# 74HC595.net
KiCad netlist of a schematic drawn in Altium Designer
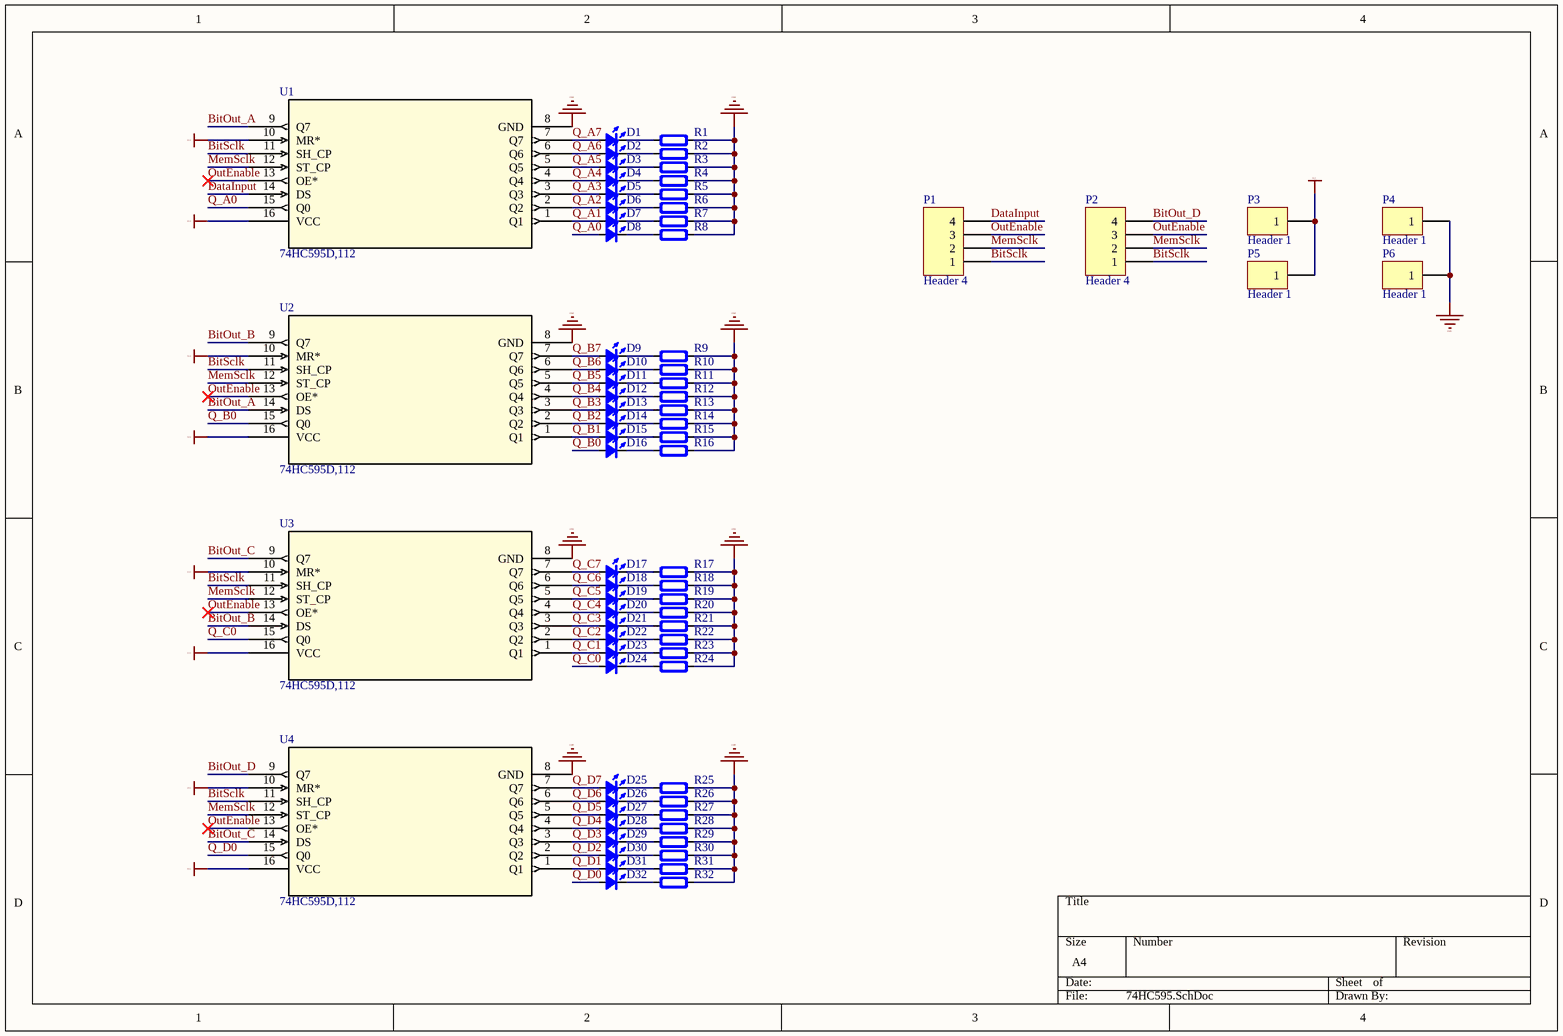
[diagram p0: 74HC595.SchDoc]

(export (version "E")
  (design (tool "Eeschema 10.0.6"))
  (components
    (comp (ref "D1")
      (value "color?")
      (footprint "PCB_ActiveLED:LED_0805_RED")
      (description "LED")
      (libsource (lib "EspPov") (part "LED_0805"))
    )
    (comp (ref "D2")
      (value "color?")
      (footprint "PCB_ActiveLED:LED_0805_RED")
      (description "LED")
      (libsource (lib "EspPov") (part "LED_0805"))
    )
    (comp (ref "D3")
      (value "color?")
      (footprint "PCB_ActiveLED:LED_0805_RED")
      (description "LED")
      (libsource (lib "EspPov") (part "LED_0805"))
    )
    (comp (ref "D4")
      (value "color?")
      (footprint "PCB_ActiveLED:LED_0805_RED")
      (description "LED")
      (libsource (lib "EspPov") (part "LED_0805"))
    )
    (comp (ref "D5")
      (value "color?")
      (footprint "PCB_ActiveLED:LED_0805_RED")
      (description "LED")
      (libsource (lib "EspPov") (part "LED_0805"))
    )
    (comp (ref "D6")
      (value "color?")
      (footprint "PCB_ActiveLED:LED_0805_RED")
      (description "LED")
      (libsource (lib "EspPov") (part "LED_0805"))
    )
    (comp (ref "D7")
      (value "color?")
      (footprint "PCB_ActiveLED:LED_0805_RED")
      (description "LED")
      (libsource (lib "EspPov") (part "LED_0805"))
    )
    (comp (ref "D8")
      (value "color?")
      (footprint "PCB_ActiveLED:LED_0805_RED")
      (description "LED")
      (libsource (lib "EspPov") (part "LED_0805"))
    )
    (comp (ref "D9")
      (value "color?")
      (footprint "PCB_ActiveLED:LED_0805_RED")
      (description "LED")
      (libsource (lib "EspPov") (part "LED_0805"))
    )
    (comp (ref "D10")
      (value "color?")
      (footprint "PCB_ActiveLED:LED_0805_RED")
      (description "LED")
      (libsource (lib "EspPov") (part "LED_0805"))
    )
    (comp (ref "D11")
      (value "color?")
      (footprint "PCB_ActiveLED:LED_0805_RED")
      (description "LED")
      (libsource (lib "EspPov") (part "LED_0805"))
    )
    (comp (ref "D12")
      (value "color?")
      (footprint "PCB_ActiveLED:LED_0805_RED")
      (description "LED")
      (libsource (lib "EspPov") (part "LED_0805"))
    )
    (comp (ref "D13")
      (value "color?")
      (footprint "PCB_ActiveLED:LED_0805_RED")
      (description "LED")
      (libsource (lib "EspPov") (part "LED_0805"))
    )
    (comp (ref "D14")
      (value "color?")
      (footprint "PCB_ActiveLED:LED_0805_RED")
      (description "LED")
      (libsource (lib "EspPov") (part "LED_0805"))
    )
    (comp (ref "D15")
      (value "color?")
      (footprint "PCB_ActiveLED:LED_0805_RED")
      (description "LED")
      (libsource (lib "EspPov") (part "LED_0805"))
    )
    (comp (ref "D16")
      (value "color?")
      (footprint "PCB_ActiveLED:LED_0805_RED")
      (description "LED")
      (libsource (lib "EspPov") (part "LED_0805"))
    )
    (comp (ref "D17")
      (value "color?")
      (footprint "PCB_ActiveLED:LED_0805_RED")
      (description "LED")
      (libsource (lib "EspPov") (part "LED_0805"))
    )
    (comp (ref "D18")
      (value "color?")
      (footprint "PCB_ActiveLED:LED_0805_RED")
      (description "LED")
      (libsource (lib "EspPov") (part "LED_0805"))
    )
    (comp (ref "D19")
      (value "color?")
      (footprint "PCB_ActiveLED:LED_0805_RED")
      (description "LED")
      (libsource (lib "EspPov") (part "LED_0805"))
    )
    (comp (ref "D20")
      (value "color?")
      (footprint "PCB_ActiveLED:LED_0805_RED")
      (description "LED")
      (libsource (lib "EspPov") (part "LED_0805"))
    )
    (comp (ref "D21")
      (value "color?")
      (footprint "PCB_ActiveLED:LED_0805_RED")
      (description "LED")
      (libsource (lib "EspPov") (part "LED_0805"))
    )
    (comp (ref "D22")
      (value "color?")
      (footprint "PCB_ActiveLED:LED_0805_RED")
      (description "LED")
      (libsource (lib "EspPov") (part "LED_0805"))
    )
    (comp (ref "D23")
      (value "color?")
      (footprint "PCB_ActiveLED:LED_0805_RED")
      (description "LED")
      (libsource (lib "EspPov") (part "LED_0805"))
    )
    (comp (ref "D24")
      (value "color?")
      (footprint "PCB_ActiveLED:LED_0805_RED")
      (description "LED")
      (libsource (lib "EspPov") (part "LED_0805"))
    )
    (comp (ref "D25")
      (value "color?")
      (footprint "PCB_ActiveLED:LED_0805_RED")
      (description "LED")
      (libsource (lib "EspPov") (part "LED_0805"))
    )
    (comp (ref "D26")
      (value "color?")
      (footprint "PCB_ActiveLED:LED_0805_RED")
      (description "LED")
      (libsource (lib "EspPov") (part "LED_0805"))
    )
    (comp (ref "D27")
      (value "color?")
      (footprint "PCB_ActiveLED:LED_0805_RED")
      (description "LED")
      (libsource (lib "EspPov") (part "LED_0805"))
    )
    (comp (ref "D28")
      (value "color?")
      (footprint "PCB_ActiveLED:LED_0805_RED")
      (description "LED")
      (libsource (lib "EspPov") (part "LED_0805"))
    )
    (comp (ref "D29")
      (value "color?")
      (footprint "PCB_ActiveLED:LED_0805_RED")
      (description "LED")
      (libsource (lib "EspPov") (part "LED_0805"))
    )
    (comp (ref "D30")
      (value "color?")
      (footprint "PCB_ActiveLED:LED_0805_RED")
      (description "LED")
      (libsource (lib "EspPov") (part "LED_0805"))
    )
    (comp (ref "D31")
      (value "color?")
      (footprint "PCB_ActiveLED:LED_0805_RED")
      (description "LED")
      (libsource (lib "EspPov") (part "LED_0805"))
    )
    (comp (ref "D32")
      (value "color?")
      (footprint "PCB_ActiveLED:LED_0805_RED")
      (description "LED")
      (libsource (lib "EspPov") (part "LED_0805"))
    )
    (comp (ref "P1")
      (value "Header 4")
      (footprint "HDR1X4_SOP")
      (description "Header, 4-Pin")
      (fields (field (name "PUBLISHER") "Altium Limited"))
      (libsource (lib "EspPov") (part "Header 4"))
    )
    (comp (ref "P2")
      (value "Header 4")
      (footprint "HDR1X4_SOP")
      (description "Header, 4-Pin")
      (fields (field (name "PUBLISHER") "Altium Limited"))
      (libsource (lib "EspPov") (part "Header 4"))
    )
    (comp (ref "P3")
      (value "Header 1")
      (footprint "HDR1X1_SOP")
      (description "Header, 1-Pin")
      (fields (field (name "PUBLISHER") "Altium Limited"))
      (libsource (lib "EspPov") (part "Header 1"))
    )
    (comp (ref "P4")
      (value "Header 1")
      (footprint "HDR1X1_SOP")
      (description "Header, 1-Pin")
      (fields (field (name "PUBLISHER") "Altium Limited"))
      (libsource (lib "EspPov") (part "Header 1"))
    )
    (comp (ref "P5")
      (value "Header 1")
      (footprint "HDR1X1_SOP")
      (description "Header, 1-Pin")
      (fields (field (name "PUBLISHER") "Altium Limited"))
      (libsource (lib "EspPov") (part "Header 1"))
    )
    (comp (ref "P6")
      (value "Header 1")
      (footprint "HDR1X1_SOP")
      (description "Header, 1-Pin")
      (fields (field (name "PUBLISHER") "Altium Limited"))
      (libsource (lib "EspPov") (part "Header 1"))
    )
    (comp (ref "R1")
      (value "R0805")
      (footprint "RES_0805")
      (description "Resistor")
      (libsource (lib "EspPov") (part "Res_0805"))
    )
    (comp (ref "R2")
      (value "R0805")
      (footprint "RES_0805")
      (description "Resistor")
      (libsource (lib "EspPov") (part "Res_0805"))
    )
    (comp (ref "R3")
      (value "R0805")
      (footprint "RES_0805")
      (description "Resistor")
      (libsource (lib "EspPov") (part "Res_0805"))
    )
    (comp (ref "R4")
      (value "R0805")
      (footprint "RES_0805")
      (description "Resistor")
      (libsource (lib "EspPov") (part "Res_0805"))
    )
    (comp (ref "R5")
      (value "R0805")
      (footprint "RES_0805")
      (description "Resistor")
      (libsource (lib "EspPov") (part "Res_0805"))
    )
    (comp (ref "R6")
      (value "R0805")
      (footprint "RES_0805")
      (description "Resistor")
      (libsource (lib "EspPov") (part "Res_0805"))
    )
    (comp (ref "R7")
      (value "R0805")
      (footprint "RES_0805")
      (description "Resistor")
      (libsource (lib "EspPov") (part "Res_0805"))
    )
    (comp (ref "R8")
      (value "R0805")
      (footprint "RES_0805")
      (description "Resistor")
      (libsource (lib "EspPov") (part "Res_0805"))
    )
    (comp (ref "R9")
      (value "R0805")
      (footprint "RES_0805")
      (description "Resistor")
      (libsource (lib "EspPov") (part "Res_0805"))
    )
    (comp (ref "R10")
      (value "R0805")
      (footprint "RES_0805")
      (description "Resistor")
      (libsource (lib "EspPov") (part "Res_0805"))
    )
    (comp (ref "R11")
      (value "R0805")
      (footprint "RES_0805")
      (description "Resistor")
      (libsource (lib "EspPov") (part "Res_0805"))
    )
    (comp (ref "R12")
      (value "R0805")
      (footprint "RES_0805")
      (description "Resistor")
      (libsource (lib "EspPov") (part "Res_0805"))
    )
    (comp (ref "R13")
      (value "R0805")
      (footprint "RES_0805")
      (description "Resistor")
      (libsource (lib "EspPov") (part "Res_0805"))
    )
    (comp (ref "R14")
      (value "R0805")
      (footprint "RES_0805")
      (description "Resistor")
      (libsource (lib "EspPov") (part "Res_0805"))
    )
    (comp (ref "R15")
      (value "R0805")
      (footprint "RES_0805")
      (description "Resistor")
      (libsource (lib "EspPov") (part "Res_0805"))
    )
    (comp (ref "R16")
      (value "R0805")
      (footprint "RES_0805")
      (description "Resistor")
      (libsource (lib "EspPov") (part "Res_0805"))
    )
    (comp (ref "R17")
      (value "R0805")
      (footprint "RES_0805")
      (description "Resistor")
      (libsource (lib "EspPov") (part "Res_0805"))
    )
    (comp (ref "R18")
      (value "R0805")
      (footprint "RES_0805")
      (description "Resistor")
      (libsource (lib "EspPov") (part "Res_0805"))
    )
    (comp (ref "R19")
      (value "R0805")
      (footprint "RES_0805")
      (description "Resistor")
      (libsource (lib "EspPov") (part "Res_0805"))
    )
    (comp (ref "R20")
      (value "R0805")
      (footprint "RES_0805")
      (description "Resistor")
      (libsource (lib "EspPov") (part "Res_0805"))
    )
    (comp (ref "R21")
      (value "R0805")
      (footprint "RES_0805")
      (description "Resistor")
      (libsource (lib "EspPov") (part "Res_0805"))
    )
    (comp (ref "R22")
      (value "R0805")
      (footprint "RES_0805")
      (description "Resistor")
      (libsource (lib "EspPov") (part "Res_0805"))
    )
    (comp (ref "R23")
      (value "R0805")
      (footprint "RES_0805")
      (description "Resistor")
      (libsource (lib "EspPov") (part "Res_0805"))
    )
    (comp (ref "R24")
      (value "R0805")
      (footprint "RES_0805")
      (description "Resistor")
      (libsource (lib "EspPov") (part "Res_0805"))
    )
    (comp (ref "R25")
      (value "R0805")
      (footprint "RES_0805")
      (description "Resistor")
      (libsource (lib "EspPov") (part "Res_0805"))
    )
    (comp (ref "R26")
      (value "R0805")
      (footprint "RES_0805")
      (description "Resistor")
      (libsource (lib "EspPov") (part "Res_0805"))
    )
    (comp (ref "R27")
      (value "R0805")
      (footprint "RES_0805")
      (description "Resistor")
      (libsource (lib "EspPov") (part "Res_0805"))
    )
    (comp (ref "R28")
      (value "R0805")
      (footprint "RES_0805")
      (description "Resistor")
      (libsource (lib "EspPov") (part "Res_0805"))
    )
    (comp (ref "R29")
      (value "R0805")
      (footprint "RES_0805")
      (description "Resistor")
      (libsource (lib "EspPov") (part "Res_0805"))
    )
    (comp (ref "R30")
      (value "R0805")
      (footprint "RES_0805")
      (description "Resistor")
      (libsource (lib "EspPov") (part "Res_0805"))
    )
    (comp (ref "R31")
      (value "R0805")
      (footprint "RES_0805")
      (description "Resistor")
      (libsource (lib "EspPov") (part "Res_0805"))
    )
    (comp (ref "R32")
      (value "R0805")
      (footprint "RES_0805")
      (description "Resistor")
      (libsource (lib "EspPov") (part "Res_0805"))
    )
    (comp (ref "U1")
      (value "74HC595D,112")
      (footprint "SOT109-1_NEX")
      (description "No Description Available")
      (fields (field (name "COPYRIGHT") "Copyright (C) 2016 Accelerated Designs. All rights reserved"))
      (libsource (lib "EspPov") (part "74HC595D,112"))
    )
    (comp (ref "U2")
      (value "74HC595D,112")
      (footprint "SOT109-1_NEX")
      (description "No Description Available")
      (fields (field (name "COPYRIGHT") "Copyright (C) 2016 Accelerated Designs. All rights reserved"))
      (libsource (lib "EspPov") (part "74HC595D,112"))
    )
    (comp (ref "U3")
      (value "74HC595D,112")
      (footprint "SOT109-1_NEX")
      (description "No Description Available")
      (fields (field (name "COPYRIGHT") "Copyright (C) 2016 Accelerated Designs. All rights reserved"))
      (libsource (lib "EspPov") (part "74HC595D,112"))
    )
    (comp (ref "U4")
      (value "74HC595D,112")
      (footprint "SOT109-1_NEX")
      (description "No Description Available")
      (fields (field (name "COPYRIGHT") "Copyright (C) 2016 Accelerated Designs. All rights reserved"))
      (libsource (lib "EspPov") (part "74HC595D,112"))
    )
  )
  (nets
    (net (code "1") (name "/BitOut_A") (class "Default")
      (node (ref "U1") (pin "9") (pinfunction "Q7_9") (pintype "output"))
      (node (ref "U2") (pin "14") (pinfunction "DS_14") (pintype "input"))
    )
    (net (code "2") (name "/BitOut_B") (class "Default")
      (node (ref "U2") (pin "9") (pinfunction "Q7_9") (pintype "output"))
      (node (ref "U3") (pin "14") (pinfunction "DS_14") (pintype "input"))
    )
    (net (code "3") (name "/BitOut_C") (class "Default")
      (node (ref "U3") (pin "9") (pinfunction "Q7_9") (pintype "output"))
      (node (ref "U4") (pin "14") (pinfunction "DS_14") (pintype "input"))
    )
    (net (code "4") (name "/BitOut_D") (class "Default")
      (node (ref "P2") (pin "4") (pinfunction "4_4") (pintype "passive"))
      (node (ref "U4") (pin "9") (pinfunction "Q7_9") (pintype "output"))
    )
    (net (code "5") (name "/BitSclk") (class "Default")
      (node (ref "P1") (pin "1") (pinfunction "1_1") (pintype "passive"))
      (node (ref "P2") (pin "1") (pinfunction "1_1") (pintype "passive"))
      (node (ref "U1") (pin "11") (pinfunction "SH_CP_11") (pintype "input"))
      (node (ref "U2") (pin "11") (pinfunction "SH_CP_11") (pintype "input"))
      (node (ref "U3") (pin "11") (pinfunction "SH_CP_11") (pintype "input"))
      (node (ref "U4") (pin "11") (pinfunction "SH_CP_11") (pintype "input"))
    )
    (net (code "6") (name "/DataInput") (class "Default")
      (node (ref "P1") (pin "4") (pinfunction "4_4") (pintype "passive"))
      (node (ref "U1") (pin "14") (pinfunction "DS_14") (pintype "input"))
    )
    (net (code "7") (name "/MemSclk") (class "Default")
      (node (ref "P1") (pin "2") (pinfunction "2_2") (pintype "passive"))
      (node (ref "P2") (pin "2") (pinfunction "2_2") (pintype "passive"))
      (node (ref "U1") (pin "12") (pinfunction "ST_CP_12") (pintype "input"))
      (node (ref "U2") (pin "12") (pinfunction "ST_CP_12") (pintype "input"))
      (node (ref "U3") (pin "12") (pinfunction "ST_CP_12") (pintype "input"))
      (node (ref "U4") (pin "12") (pinfunction "ST_CP_12") (pintype "input"))
    )
    (net (code "8") (name "/OutEnable") (class "Default")
      (node (ref "P1") (pin "3") (pinfunction "3_3") (pintype "passive"))
      (node (ref "P2") (pin "3") (pinfunction "3_3") (pintype "passive"))
      (node (ref "U1") (pin "13") (pinfunction "OE*_13") (pintype "output"))
      (node (ref "U2") (pin "13") (pinfunction "OE*_13") (pintype "output"))
      (node (ref "U3") (pin "13") (pinfunction "OE*_13") (pintype "output"))
      (node (ref "U4") (pin "13") (pinfunction "OE*_13") (pintype "output"))
    )
    (net (code "9") (name "/Q_A0") (class "Default")
      (node (ref "D8") (pin "2") (pinfunction "A_2") (pintype "passive"))
      (node (ref "U1") (pin "15") (pinfunction "Q0_15") (pintype "output"))
    )
    (net (code "10") (name "/Q_A1") (class "Default")
      (node (ref "D7") (pin "2") (pinfunction "A_2") (pintype "passive"))
      (node (ref "U1") (pin "1") (pinfunction "Q1_1") (pintype "output"))
    )
    (net (code "11") (name "/Q_A2") (class "Default")
      (node (ref "D6") (pin "2") (pinfunction "A_2") (pintype "passive"))
      (node (ref "U1") (pin "2") (pinfunction "Q2_2") (pintype "output"))
    )
    (net (code "12") (name "/Q_A3") (class "Default")
      (node (ref "D5") (pin "2") (pinfunction "A_2") (pintype "passive"))
      (node (ref "U1") (pin "3") (pinfunction "Q3_3") (pintype "output"))
    )
    (net (code "13") (name "/Q_A4") (class "Default")
      (node (ref "D4") (pin "2") (pinfunction "A_2") (pintype "passive"))
      (node (ref "U1") (pin "4") (pinfunction "Q4_4") (pintype "output"))
    )
    (net (code "14") (name "/Q_A5") (class "Default")
      (node (ref "D3") (pin "2") (pinfunction "A_2") (pintype "passive"))
      (node (ref "U1") (pin "5") (pinfunction "Q5_5") (pintype "output"))
    )
    (net (code "15") (name "/Q_A6") (class "Default")
      (node (ref "D2") (pin "2") (pinfunction "A_2") (pintype "passive"))
      (node (ref "U1") (pin "6") (pinfunction "Q6_6") (pintype "output"))
    )
    (net (code "16") (name "/Q_A7") (class "Default")
      (node (ref "D1") (pin "2") (pinfunction "A_2") (pintype "passive"))
      (node (ref "U1") (pin "7") (pinfunction "Q7_7") (pintype "output"))
    )
    (net (code "17") (name "/Q_B0") (class "Default")
      (node (ref "D16") (pin "2") (pinfunction "A_2") (pintype "passive"))
      (node (ref "U2") (pin "15") (pinfunction "Q0_15") (pintype "output"))
    )
    (net (code "18") (name "/Q_B1") (class "Default")
      (node (ref "D15") (pin "2") (pinfunction "A_2") (pintype "passive"))
      (node (ref "U2") (pin "1") (pinfunction "Q1_1") (pintype "output"))
    )
    (net (code "19") (name "/Q_B2") (class "Default")
      (node (ref "D14") (pin "2") (pinfunction "A_2") (pintype "passive"))
      (node (ref "U2") (pin "2") (pinfunction "Q2_2") (pintype "output"))
    )
    (net (code "20") (name "/Q_B3") (class "Default")
      (node (ref "D13") (pin "2") (pinfunction "A_2") (pintype "passive"))
      (node (ref "U2") (pin "3") (pinfunction "Q3_3") (pintype "output"))
    )
    (net (code "21") (name "/Q_B4") (class "Default")
      (node (ref "D12") (pin "2") (pinfunction "A_2") (pintype "passive"))
      (node (ref "U2") (pin "4") (pinfunction "Q4_4") (pintype "output"))
    )
    (net (code "22") (name "/Q_B5") (class "Default")
      (node (ref "D11") (pin "2") (pinfunction "A_2") (pintype "passive"))
      (node (ref "U2") (pin "5") (pinfunction "Q5_5") (pintype "output"))
    )
    (net (code "23") (name "/Q_B6") (class "Default")
      (node (ref "D10") (pin "2") (pinfunction "A_2") (pintype "passive"))
      (node (ref "U2") (pin "6") (pinfunction "Q6_6") (pintype "output"))
    )
    (net (code "24") (name "/Q_B7") (class "Default")
      (node (ref "D9") (pin "2") (pinfunction "A_2") (pintype "passive"))
      (node (ref "U2") (pin "7") (pinfunction "Q7_7") (pintype "output"))
    )
    (net (code "25") (name "/Q_C0") (class "Default")
      (node (ref "D24") (pin "2") (pinfunction "A_2") (pintype "passive"))
      (node (ref "U3") (pin "15") (pinfunction "Q0_15") (pintype "output"))
    )
    (net (code "26") (name "/Q_C1") (class "Default")
      (node (ref "D23") (pin "2") (pinfunction "A_2") (pintype "passive"))
      (node (ref "U3") (pin "1") (pinfunction "Q1_1") (pintype "output"))
    )
    (net (code "27") (name "/Q_C2") (class "Default")
      (node (ref "D22") (pin "2") (pinfunction "A_2") (pintype "passive"))
      (node (ref "U3") (pin "2") (pinfunction "Q2_2") (pintype "output"))
    )
    (net (code "28") (name "/Q_C3") (class "Default")
      (node (ref "D21") (pin "2") (pinfunction "A_2") (pintype "passive"))
      (node (ref "U3") (pin "3") (pinfunction "Q3_3") (pintype "output"))
    )
    (net (code "29") (name "/Q_C4") (class "Default")
      (node (ref "D20") (pin "2") (pinfunction "A_2") (pintype "passive"))
      (node (ref "U3") (pin "4") (pinfunction "Q4_4") (pintype "output"))
    )
    (net (code "30") (name "/Q_C5") (class "Default")
      (node (ref "D19") (pin "2") (pinfunction "A_2") (pintype "passive"))
      (node (ref "U3") (pin "5") (pinfunction "Q5_5") (pintype "output"))
    )
    (net (code "31") (name "/Q_C6") (class "Default")
      (node (ref "D18") (pin "2") (pinfunction "A_2") (pintype "passive"))
      (node (ref "U3") (pin "6") (pinfunction "Q6_6") (pintype "output"))
    )
    (net (code "32") (name "/Q_C7") (class "Default")
      (node (ref "D17") (pin "2") (pinfunction "A_2") (pintype "passive"))
      (node (ref "U3") (pin "7") (pinfunction "Q7_7") (pintype "output"))
    )
    (net (code "33") (name "/Q_D0") (class "Default")
      (node (ref "D32") (pin "2") (pinfunction "A_2") (pintype "passive"))
      (node (ref "U4") (pin "15") (pinfunction "Q0_15") (pintype "output"))
    )
    (net (code "34") (name "/Q_D1") (class "Default")
      (node (ref "D31") (pin "2") (pinfunction "A_2") (pintype "passive"))
      (node (ref "U4") (pin "1") (pinfunction "Q1_1") (pintype "output"))
    )
    (net (code "35") (name "/Q_D2") (class "Default")
      (node (ref "D30") (pin "2") (pinfunction "A_2") (pintype "passive"))
      (node (ref "U4") (pin "2") (pinfunction "Q2_2") (pintype "output"))
    )
    (net (code "36") (name "/Q_D3") (class "Default")
      (node (ref "D29") (pin "2") (pinfunction "A_2") (pintype "passive"))
      (node (ref "U4") (pin "3") (pinfunction "Q3_3") (pintype "output"))
    )
    (net (code "37") (name "/Q_D4") (class "Default")
      (node (ref "D28") (pin "2") (pinfunction "A_2") (pintype "passive"))
      (node (ref "U4") (pin "4") (pinfunction "Q4_4") (pintype "output"))
    )
    (net (code "38") (name "/Q_D5") (class "Default")
      (node (ref "D27") (pin "2") (pinfunction "A_2") (pintype "passive"))
      (node (ref "U4") (pin "5") (pinfunction "Q5_5") (pintype "output"))
    )
    (net (code "39") (name "/Q_D6") (class "Default")
      (node (ref "D26") (pin "2") (pinfunction "A_2") (pintype "passive"))
      (node (ref "U4") (pin "6") (pinfunction "Q6_6") (pintype "output"))
    )
    (net (code "40") (name "/Q_D7") (class "Default")
      (node (ref "D25") (pin "2") (pinfunction "A_2") (pintype "passive"))
      (node (ref "U4") (pin "7") (pinfunction "Q7_7") (pintype "output"))
    )
    (net (code "41") (name "GND") (class "Default")
      (node (ref "P4") (pin "1") (pinfunction "1_1") (pintype "passive"))
      (node (ref "P6") (pin "1") (pinfunction "1_1") (pintype "passive"))
      (node (ref "R1") (pin "2") (pinfunction "2_2") (pintype "passive"))
      (node (ref "R10") (pin "2") (pinfunction "2_2") (pintype "passive"))
      (node (ref "R11") (pin "2") (pinfunction "2_2") (pintype "passive"))
      (node (ref "R12") (pin "2") (pinfunction "2_2") (pintype "passive"))
      (node (ref "R13") (pin "2") (pinfunction "2_2") (pintype "passive"))
      (node (ref "R14") (pin "2") (pinfunction "2_2") (pintype "passive"))
      (node (ref "R15") (pin "2") (pinfunction "2_2") (pintype "passive"))
      (node (ref "R16") (pin "2") (pinfunction "2_2") (pintype "passive"))
      (node (ref "R17") (pin "2") (pinfunction "2_2") (pintype "passive"))
      (node (ref "R18") (pin "2") (pinfunction "2_2") (pintype "passive"))
      (node (ref "R19") (pin "2") (pinfunction "2_2") (pintype "passive"))
      (node (ref "R2") (pin "2") (pinfunction "2_2") (pintype "passive"))
      (node (ref "R20") (pin "2") (pinfunction "2_2") (pintype "passive"))
      (node (ref "R21") (pin "2") (pinfunction "2_2") (pintype "passive"))
      (node (ref "R22") (pin "2") (pinfunction "2_2") (pintype "passive"))
      (node (ref "R23") (pin "2") (pinfunction "2_2") (pintype "passive"))
      (node (ref "R24") (pin "2") (pinfunction "2_2") (pintype "passive"))
      (node (ref "R25") (pin "2") (pinfunction "2_2") (pintype "passive"))
      (node (ref "R26") (pin "2") (pinfunction "2_2") (pintype "passive"))
      (node (ref "R27") (pin "2") (pinfunction "2_2") (pintype "passive"))
      (node (ref "R28") (pin "2") (pinfunction "2_2") (pintype "passive"))
      (node (ref "R29") (pin "2") (pinfunction "2_2") (pintype "passive"))
      (node (ref "R3") (pin "2") (pinfunction "2_2") (pintype "passive"))
      (node (ref "R30") (pin "2") (pinfunction "2_2") (pintype "passive"))
      (node (ref "R31") (pin "2") (pinfunction "2_2") (pintype "passive"))
      (node (ref "R32") (pin "2") (pinfunction "2_2") (pintype "passive"))
      (node (ref "R4") (pin "2") (pinfunction "2_2") (pintype "passive"))
      (node (ref "R5") (pin "2") (pinfunction "2_2") (pintype "passive"))
      (node (ref "R6") (pin "2") (pinfunction "2_2") (pintype "passive"))
      (node (ref "R7") (pin "2") (pinfunction "2_2") (pintype "passive"))
      (node (ref "R8") (pin "2") (pinfunction "2_2") (pintype "passive"))
      (node (ref "R9") (pin "2") (pinfunction "2_2") (pintype "passive"))
      (node (ref "U1") (pin "8") (pinfunction "GND_8") (pintype "power_in"))
      (node (ref "U2") (pin "8") (pinfunction "GND_8") (pintype "power_in"))
      (node (ref "U3") (pin "8") (pinfunction "GND_8") (pintype "power_in"))
      (node (ref "U4") (pin "8") (pinfunction "GND_8") (pintype "power_in"))
    )
    (net (code "42") (name "Net-(D1-K)") (class "Default")
      (node (ref "D1") (pin "1") (pinfunction "K_1") (pintype "passive"))
      (node (ref "R1") (pin "1") (pinfunction "1_1") (pintype "passive"))
    )
    (net (code "43") (name "Net-(D2-K)") (class "Default")
      (node (ref "D2") (pin "1") (pinfunction "K_1") (pintype "passive"))
      (node (ref "R2") (pin "1") (pinfunction "1_1") (pintype "passive"))
    )
    (net (code "44") (name "Net-(D3-K)") (class "Default")
      (node (ref "D3") (pin "1") (pinfunction "K_1") (pintype "passive"))
      (node (ref "R3") (pin "1") (pinfunction "1_1") (pintype "passive"))
    )
    (net (code "45") (name "Net-(D4-K)") (class "Default")
      (node (ref "D4") (pin "1") (pinfunction "K_1") (pintype "passive"))
      (node (ref "R4") (pin "1") (pinfunction "1_1") (pintype "passive"))
    )
    (net (code "46") (name "Net-(D5-K)") (class "Default")
      (node (ref "D5") (pin "1") (pinfunction "K_1") (pintype "passive"))
      (node (ref "R5") (pin "1") (pinfunction "1_1") (pintype "passive"))
    )
    (net (code "47") (name "Net-(D6-K)") (class "Default")
      (node (ref "D6") (pin "1") (pinfunction "K_1") (pintype "passive"))
      (node (ref "R6") (pin "1") (pinfunction "1_1") (pintype "passive"))
    )
    (net (code "48") (name "Net-(D7-K)") (class "Default")
      (node (ref "D7") (pin "1") (pinfunction "K_1") (pintype "passive"))
      (node (ref "R7") (pin "1") (pinfunction "1_1") (pintype "passive"))
    )
    (net (code "49") (name "Net-(D8-K)") (class "Default")
      (node (ref "D8") (pin "1") (pinfunction "K_1") (pintype "passive"))
      (node (ref "R8") (pin "1") (pinfunction "1_1") (pintype "passive"))
    )
    (net (code "50") (name "Net-(D9-K)") (class "Default")
      (node (ref "D9") (pin "1") (pinfunction "K_1") (pintype "passive"))
      (node (ref "R9") (pin "1") (pinfunction "1_1") (pintype "passive"))
    )
    (net (code "51") (name "Net-(D10-K)") (class "Default")
      (node (ref "D10") (pin "1") (pinfunction "K_1") (pintype "passive"))
      (node (ref "R10") (pin "1") (pinfunction "1_1") (pintype "passive"))
    )
    (net (code "52") (name "Net-(D11-K)") (class "Default")
      (node (ref "D11") (pin "1") (pinfunction "K_1") (pintype "passive"))
      (node (ref "R11") (pin "1") (pinfunction "1_1") (pintype "passive"))
    )
    (net (code "53") (name "Net-(D12-K)") (class "Default")
      (node (ref "D12") (pin "1") (pinfunction "K_1") (pintype "passive"))
      (node (ref "R12") (pin "1") (pinfunction "1_1") (pintype "passive"))
    )
    (net (code "54") (name "Net-(D13-K)") (class "Default")
      (node (ref "D13") (pin "1") (pinfunction "K_1") (pintype "passive"))
      (node (ref "R13") (pin "1") (pinfunction "1_1") (pintype "passive"))
    )
    (net (code "55") (name "Net-(D14-K)") (class "Default")
      (node (ref "D14") (pin "1") (pinfunction "K_1") (pintype "passive"))
      (node (ref "R14") (pin "1") (pinfunction "1_1") (pintype "passive"))
    )
    (net (code "56") (name "Net-(D15-K)") (class "Default")
      (node (ref "D15") (pin "1") (pinfunction "K_1") (pintype "passive"))
      (node (ref "R15") (pin "1") (pinfunction "1_1") (pintype "passive"))
    )
    (net (code "57") (name "Net-(D16-K)") (class "Default")
      (node (ref "D16") (pin "1") (pinfunction "K_1") (pintype "passive"))
      (node (ref "R16") (pin "1") (pinfunction "1_1") (pintype "passive"))
    )
    (net (code "58") (name "Net-(D17-K)") (class "Default")
      (node (ref "D17") (pin "1") (pinfunction "K_1") (pintype "passive"))
      (node (ref "R17") (pin "1") (pinfunction "1_1") (pintype "passive"))
    )
    (net (code "59") (name "Net-(D18-K)") (class "Default")
      (node (ref "D18") (pin "1") (pinfunction "K_1") (pintype "passive"))
      (node (ref "R18") (pin "1") (pinfunction "1_1") (pintype "passive"))
    )
    (net (code "60") (name "Net-(D19-K)") (class "Default")
      (node (ref "D19") (pin "1") (pinfunction "K_1") (pintype "passive"))
      (node (ref "R19") (pin "1") (pinfunction "1_1") (pintype "passive"))
    )
    (net (code "61") (name "Net-(D20-K)") (class "Default")
      (node (ref "D20") (pin "1") (pinfunction "K_1") (pintype "passive"))
      (node (ref "R20") (pin "1") (pinfunction "1_1") (pintype "passive"))
    )
    (net (code "62") (name "Net-(D21-K)") (class "Default")
      (node (ref "D21") (pin "1") (pinfunction "K_1") (pintype "passive"))
      (node (ref "R21") (pin "1") (pinfunction "1_1") (pintype "passive"))
    )
    (net (code "63") (name "Net-(D22-K)") (class "Default")
      (node (ref "D22") (pin "1") (pinfunction "K_1") (pintype "passive"))
      (node (ref "R22") (pin "1") (pinfunction "1_1") (pintype "passive"))
    )
    (net (code "64") (name "Net-(D23-K)") (class "Default")
      (node (ref "D23") (pin "1") (pinfunction "K_1") (pintype "passive"))
      (node (ref "R23") (pin "1") (pinfunction "1_1") (pintype "passive"))
    )
    (net (code "65") (name "Net-(D24-K)") (class "Default")
      (node (ref "D24") (pin "1") (pinfunction "K_1") (pintype "passive"))
      (node (ref "R24") (pin "1") (pinfunction "1_1") (pintype "passive"))
    )
    (net (code "66") (name "Net-(D25-K)") (class "Default")
      (node (ref "D25") (pin "1") (pinfunction "K_1") (pintype "passive"))
      (node (ref "R25") (pin "1") (pinfunction "1_1") (pintype "passive"))
    )
    (net (code "67") (name "Net-(D26-K)") (class "Default")
      (node (ref "D26") (pin "1") (pinfunction "K_1") (pintype "passive"))
      (node (ref "R26") (pin "1") (pinfunction "1_1") (pintype "passive"))
    )
    (net (code "68") (name "Net-(D27-K)") (class "Default")
      (node (ref "D27") (pin "1") (pinfunction "K_1") (pintype "passive"))
      (node (ref "R27") (pin "1") (pinfunction "1_1") (pintype "passive"))
    )
    (net (code "69") (name "Net-(D28-K)") (class "Default")
      (node (ref "D28") (pin "1") (pinfunction "K_1") (pintype "passive"))
      (node (ref "R28") (pin "1") (pinfunction "1_1") (pintype "passive"))
    )
    (net (code "70") (name "Net-(D29-K)") (class "Default")
      (node (ref "D29") (pin "1") (pinfunction "K_1") (pintype "passive"))
      (node (ref "R29") (pin "1") (pinfunction "1_1") (pintype "passive"))
    )
    (net (code "71") (name "Net-(D30-K)") (class "Default")
      (node (ref "D30") (pin "1") (pinfunction "K_1") (pintype "passive"))
      (node (ref "R30") (pin "1") (pinfunction "1_1") (pintype "passive"))
    )
    (net (code "72") (name "Net-(D31-K)") (class "Default")
      (node (ref "D31") (pin "1") (pinfunction "K_1") (pintype "passive"))
      (node (ref "R31") (pin "1") (pinfunction "1_1") (pintype "passive"))
    )
    (net (code "73") (name "Net-(D32-K)") (class "Default")
      (node (ref "D32") (pin "1") (pinfunction "K_1") (pintype "passive"))
      (node (ref "R32") (pin "1") (pinfunction "1_1") (pintype "passive"))
    )
    (net (code "74") (name "VCC") (class "Default")
      (node (ref "P3") (pin "1") (pinfunction "1_1") (pintype "passive"))
      (node (ref "P5") (pin "1") (pinfunction "1_1") (pintype "passive"))
      (node (ref "U1") (pin "10") (pinfunction "MR*_10") (pintype "input"))
      (node (ref "U1") (pin "16") (pinfunction "VCC_16") (pintype "power_in"))
      (node (ref "U2") (pin "10") (pinfunction "MR*_10") (pintype "input"))
      (node (ref "U2") (pin "16") (pinfunction "VCC_16") (pintype "power_in"))
      (node (ref "U3") (pin "10") (pinfunction "MR*_10") (pintype "input"))
      (node (ref "U3") (pin "16") (pinfunction "VCC_16") (pintype "power_in"))
      (node (ref "U4") (pin "10") (pinfunction "MR*_10") (pintype "input"))
      (node (ref "U4") (pin "16") (pinfunction "VCC_16") (pintype "power_in"))
    )
  )
)
